# protections.net
KiCad netlist of a schematic drawn in Altium Designer
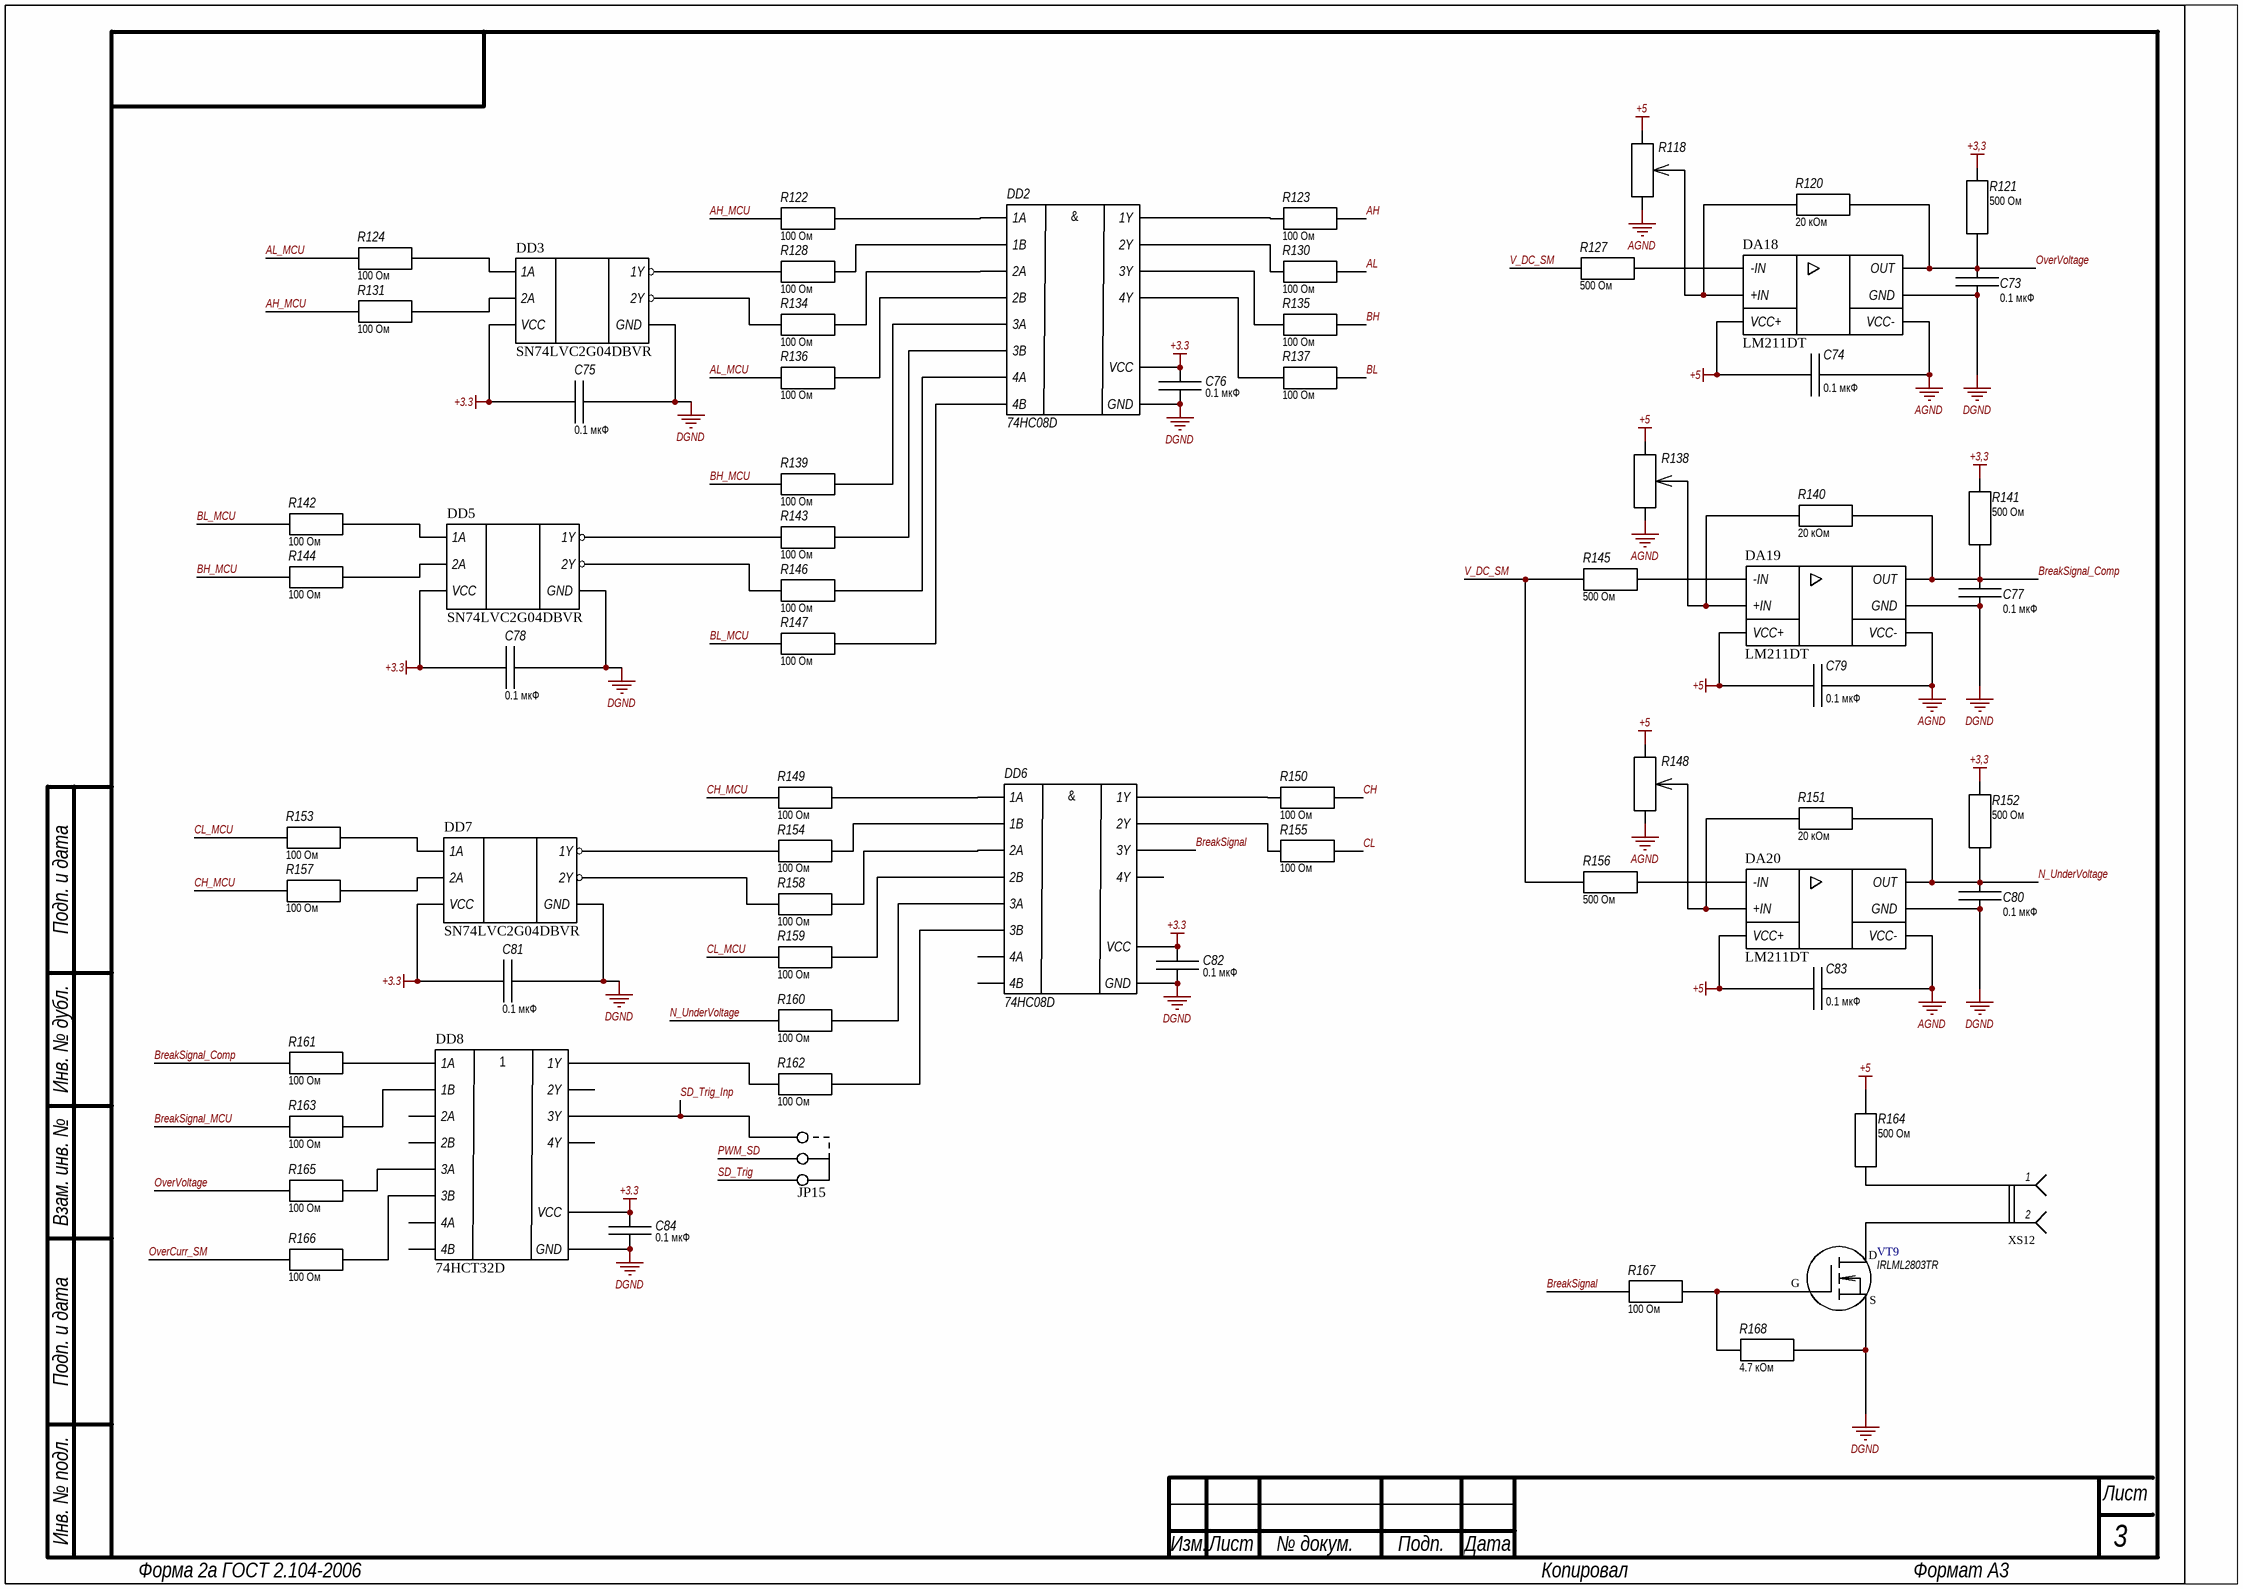
[diagram p0: protections.SchDoc]

(export (version "E")
  (design (tool "Eeschema 10.0.6"))
  (components
    (comp (ref "C73")
      (value "0.1 мкФ")
      (footprint "CC0603")
      (fields (field (name "VOLTAGE") "16В") (field (name "Comment") "Capacitor"))
      (libsource (lib "Main_components") (part "Capacitor"))
    )
    (comp (ref "C74")
      (value "0.1 мкФ")
      (footprint "CC0603")
      (fields (field (name "VOLTAGE") "16В") (field (name "Comment") "Capacitor"))
      (libsource (lib "Main_components") (part "Capacitor"))
    )
    (comp (ref "C75")
      (value "0.1 мкФ")
      (footprint "CC0603")
      (fields (field (name "VOLTAGE") "16В") (field (name "Comment") "Capacitor"))
      (libsource (lib "Main_components") (part "Capacitor"))
    )
    (comp (ref "C76")
      (value "0.1 мкФ")
      (footprint "CC0603")
      (fields (field (name "VOLTAGE") "16В") (field (name "Comment") "Capacitor"))
      (libsource (lib "Main_components") (part "Capacitor"))
    )
    (comp (ref "C77")
      (value "0.1 мкФ")
      (footprint "CC0603")
      (fields (field (name "VOLTAGE") "16В") (field (name "Comment") "Capacitor"))
      (libsource (lib "Main_components") (part "Capacitor"))
    )
    (comp (ref "C78")
      (value "0.1 мкФ")
      (footprint "CC0603")
      (fields (field (name "VOLTAGE") "16В") (field (name "Comment") "Capacitor"))
      (libsource (lib "Main_components") (part "Capacitor"))
    )
    (comp (ref "C79")
      (value "0.1 мкФ")
      (footprint "CC0603")
      (fields (field (name "VOLTAGE") "16В") (field (name "Comment") "Capacitor"))
      (libsource (lib "Main_components") (part "Capacitor"))
    )
    (comp (ref "C80")
      (value "0.1 мкФ")
      (footprint "CC0603")
      (fields (field (name "VOLTAGE") "16В") (field (name "Comment") "Capacitor"))
      (libsource (lib "Main_components") (part "Capacitor"))
    )
    (comp (ref "C81")
      (value "0.1 мкФ")
      (footprint "CC0603")
      (fields (field (name "VOLTAGE") "16В") (field (name "Comment") "Capacitor"))
      (libsource (lib "Main_components") (part "Capacitor"))
    )
    (comp (ref "C82")
      (value "0.1 мкФ")
      (footprint "CC0603")
      (fields (field (name "VOLTAGE") "16В") (field (name "Comment") "Capacitor"))
      (libsource (lib "Main_components") (part "Capacitor"))
    )
    (comp (ref "C83")
      (value "0.1 мкФ")
      (footprint "CC0603")
      (fields (field (name "VOLTAGE") "16В") (field (name "Comment") "Capacitor"))
      (libsource (lib "Main_components") (part "Capacitor"))
    )
    (comp (ref "C84")
      (value "0.1 мкФ")
      (footprint "CC0603")
      (fields (field (name "VOLTAGE") "16В") (field (name "Comment") "Capacitor"))
      (libsource (lib "Main_components") (part "Capacitor"))
    )
    (comp (ref "DA18")
      (value "LM211DT")
      (footprint "SO8")
      (description "Компаратор")
      (libsource (lib "Microcircuits") (part "LM211DT"))
    )
    (comp (ref "DA19")
      (value "LM211DT")
      (footprint "SO8")
      (description "Компаратор")
      (libsource (lib "Microcircuits") (part "LM211DT"))
    )
    (comp (ref "DA20")
      (value "LM211DT")
      (footprint "SO8")
      (description "Компаратор")
      (libsource (lib "Microcircuits") (part "LM211DT"))
    )
    (comp (ref "DD2")
      (value "74HC08D")
      (footprint "SO14")
      (description "Логическая ИС, логическая функция 2И [SO-14]")
      (libsource (lib "Microcircuits") (part "74HC08D"))
    )
    (comp (ref "DD3")
      (value "SN74LVC2G04DBVR")
      (footprint "SOT-23-6")
      (description "Двойной инвертер [SOT-23-6]")
      (libsource (lib "Microcircuits") (part "SN74LVC2G04DBVR"))
    )
    (comp (ref "DD5")
      (value "SN74LVC2G04DBVR")
      (footprint "SOT-23-6")
      (description "Двойной инвертер [SOT-23-6]")
      (libsource (lib "Microcircuits") (part "SN74LVC2G04DBVR"))
    )
    (comp (ref "DD6")
      (value "74HC08D")
      (footprint "SO14")
      (description "Логическая ИС, логическая функция 2И [SO-14]")
      (libsource (lib "Microcircuits") (part "74HC08D"))
    )
    (comp (ref "DD7")
      (value "SN74LVC2G04DBVR")
      (footprint "SOT-23-6")
      (description "Двойной инвертер [SOT-23-6]")
      (libsource (lib "Microcircuits") (part "SN74LVC2G04DBVR"))
    )
    (comp (ref "DD8")
      (value "74HCT32D")
      (footprint "SO14")
      (description "Логическая ИС, логическая функция 2ИЛИ [SO-14]")
      (libsource (lib "Microcircuits") (part "74HCT32D"))
    )
    (comp (ref "JP15") (value "Jumper") (footprint "PLS3") (libsource (lib "Connectors") (part "Jumper")))
    (comp (ref "R118") (value "pot") (footprint "3296W") (libsource (lib "Main_components") (part "pot")))
    (comp (ref "R120")
      (value "20 кОм")
      (footprint "RC0805")
      (fields (field (name "POWER") "125 мВт") (field (name "Comment") "Resistor"))
      (libsource (lib "Main_components") (part "Resistor"))
    )
    (comp (ref "R121")
      (value "500 Ом")
      (footprint "RC0805")
      (fields (field (name "POWER") "125 мВт") (field (name "Comment") "Resistor"))
      (libsource (lib "Main_components") (part "Resistor"))
    )
    (comp (ref "R122")
      (value "100 Ом")
      (footprint "RC0603")
      (fields (field (name "POWER") "100 мВт") (field (name "Comment") "Resistor"))
      (libsource (lib "Main_components") (part "Resistor"))
    )
    (comp (ref "R123")
      (value "100 Ом")
      (footprint "RC0603")
      (fields (field (name "POWER") "100 мВт") (field (name "Comment") "Resistor"))
      (libsource (lib "Main_components") (part "Resistor"))
    )
    (comp (ref "R124")
      (value "100 Ом")
      (footprint "RC0603")
      (fields (field (name "POWER") "100 мВт") (field (name "Comment") "Resistor"))
      (libsource (lib "Main_components") (part "Resistor"))
    )
    (comp (ref "R127")
      (value "500 Ом")
      (footprint "RC0805")
      (fields (field (name "POWER") "125 мВт") (field (name "Comment") "Resistor"))
      (libsource (lib "Main_components") (part "Resistor"))
    )
    (comp (ref "R128")
      (value "100 Ом")
      (footprint "RC0603")
      (fields (field (name "POWER") "100 мВт") (field (name "Comment") "Resistor"))
      (libsource (lib "Main_components") (part "Resistor"))
    )
    (comp (ref "R130")
      (value "100 Ом")
      (footprint "RC0603")
      (fields (field (name "POWER") "100 мВт") (field (name "Comment") "Resistor"))
      (libsource (lib "Main_components") (part "Resistor"))
    )
    (comp (ref "R131")
      (value "100 Ом")
      (footprint "RC0603")
      (fields (field (name "POWER") "100 мВт") (field (name "Comment") "Resistor"))
      (libsource (lib "Main_components") (part "Resistor"))
    )
    (comp (ref "R134")
      (value "100 Ом")
      (footprint "RC0603")
      (fields (field (name "POWER") "100 мВт") (field (name "Comment") "Resistor"))
      (libsource (lib "Main_components") (part "Resistor"))
    )
    (comp (ref "R135")
      (value "100 Ом")
      (footprint "RC0603")
      (fields (field (name "POWER") "100 мВт") (field (name "Comment") "Resistor"))
      (libsource (lib "Main_components") (part "Resistor"))
    )
    (comp (ref "R136")
      (value "100 Ом")
      (footprint "RC0603")
      (fields (field (name "POWER") "100 мВт") (field (name "Comment") "Resistor"))
      (libsource (lib "Main_components") (part "Resistor"))
    )
    (comp (ref "R137")
      (value "100 Ом")
      (footprint "RC0603")
      (fields (field (name "POWER") "100 мВт") (field (name "Comment") "Resistor"))
      (libsource (lib "Main_components") (part "Resistor"))
    )
    (comp (ref "R138") (value "pot") (footprint "3296W") (libsource (lib "Main_components") (part "pot")))
    (comp (ref "R139")
      (value "100 Ом")
      (footprint "RC0603")
      (fields (field (name "POWER") "100 мВт") (field (name "Comment") "Resistor"))
      (libsource (lib "Main_components") (part "Resistor"))
    )
    (comp (ref "R140")
      (value "20 кОм")
      (footprint "RC0805")
      (fields (field (name "POWER") "125 мВт") (field (name "Comment") "Resistor"))
      (libsource (lib "Main_components") (part "Resistor"))
    )
    (comp (ref "R141")
      (value "500 Ом")
      (footprint "RC0805")
      (fields (field (name "POWER") "125 мВт") (field (name "Comment") "Resistor"))
      (libsource (lib "Main_components") (part "Resistor"))
    )
    (comp (ref "R142")
      (value "100 Ом")
      (footprint "RC0603")
      (fields (field (name "POWER") "100 мВт") (field (name "Comment") "Resistor"))
      (libsource (lib "Main_components") (part "Resistor"))
    )
    (comp (ref "R143")
      (value "100 Ом")
      (footprint "RC0603")
      (fields (field (name "POWER") "100 мВт") (field (name "Comment") "Resistor"))
      (libsource (lib "Main_components") (part "Resistor"))
    )
    (comp (ref "R144")
      (value "100 Ом")
      (footprint "RC0603")
      (fields (field (name "POWER") "100 мВт") (field (name "Comment") "Resistor"))
      (libsource (lib "Main_components") (part "Resistor"))
    )
    (comp (ref "R145")
      (value "500 Ом")
      (footprint "RC0805")
      (fields (field (name "POWER") "125 мВт") (field (name "Comment") "Resistor"))
      (libsource (lib "Main_components") (part "Resistor"))
    )
    (comp (ref "R146")
      (value "100 Ом")
      (footprint "RC0603")
      (fields (field (name "POWER") "100 мВт") (field (name "Comment") "Resistor"))
      (libsource (lib "Main_components") (part "Resistor"))
    )
    (comp (ref "R147")
      (value "100 Ом")
      (footprint "RC0603")
      (fields (field (name "POWER") "100 мВт") (field (name "Comment") "Resistor"))
      (libsource (lib "Main_components") (part "Resistor"))
    )
    (comp (ref "R148") (value "pot") (footprint "3296W") (libsource (lib "Main_components") (part "pot")))
    (comp (ref "R149")
      (value "100 Ом")
      (footprint "RC0603")
      (fields (field (name "POWER") "100 мВт") (field (name "Comment") "Resistor"))
      (libsource (lib "Main_components") (part "Resistor"))
    )
    (comp (ref "R150")
      (value "100 Ом")
      (footprint "RC0603")
      (fields (field (name "POWER") "100 мВт") (field (name "Comment") "Resistor"))
      (libsource (lib "Main_components") (part "Resistor"))
    )
    (comp (ref "R151")
      (value "20 кОм")
      (footprint "RC0805")
      (fields (field (name "POWER") "125 мВт") (field (name "Comment") "Resistor"))
      (libsource (lib "Main_components") (part "Resistor"))
    )
    (comp (ref "R152")
      (value "500 Ом")
      (footprint "RC0805")
      (fields (field (name "POWER") "125 мВт") (field (name "Comment") "Resistor"))
      (libsource (lib "Main_components") (part "Resistor"))
    )
    (comp (ref "R153")
      (value "100 Ом")
      (footprint "RC0603")
      (fields (field (name "POWER") "100 мВт") (field (name "Comment") "Resistor"))
      (libsource (lib "Main_components") (part "Resistor"))
    )
    (comp (ref "R154")
      (value "100 Ом")
      (footprint "RC0603")
      (fields (field (name "POWER") "100 мВт") (field (name "Comment") "Resistor"))
      (libsource (lib "Main_components") (part "Resistor"))
    )
    (comp (ref "R155")
      (value "100 Ом")
      (footprint "RC0603")
      (fields (field (name "POWER") "100 мВт") (field (name "Comment") "Resistor"))
      (libsource (lib "Main_components") (part "Resistor"))
    )
    (comp (ref "R156")
      (value "500 Ом")
      (footprint "RC0805")
      (fields (field (name "POWER") "125 мВт") (field (name "Comment") "Resistor"))
      (libsource (lib "Main_components") (part "Resistor"))
    )
    (comp (ref "R157")
      (value "100 Ом")
      (footprint "RC0603")
      (fields (field (name "POWER") "100 мВт") (field (name "Comment") "Resistor"))
      (libsource (lib "Main_components") (part "Resistor"))
    )
    (comp (ref "R158")
      (value "100 Ом")
      (footprint "RC0603")
      (fields (field (name "POWER") "100 мВт") (field (name "Comment") "Resistor"))
      (libsource (lib "Main_components") (part "Resistor"))
    )
    (comp (ref "R159")
      (value "100 Ом")
      (footprint "RC0603")
      (fields (field (name "POWER") "100 мВт") (field (name "Comment") "Resistor"))
      (libsource (lib "Main_components") (part "Resistor"))
    )
    (comp (ref "R160")
      (value "100 Ом")
      (footprint "RC0603")
      (fields (field (name "POWER") "100 мВт") (field (name "Comment") "Resistor"))
      (libsource (lib "Main_components") (part "Resistor"))
    )
    (comp (ref "R161")
      (value "100 Ом")
      (footprint "RC0603")
      (fields (field (name "POWER") "100 мВт") (field (name "Comment") "Resistor"))
      (libsource (lib "Main_components") (part "Resistor"))
    )
    (comp (ref "R162")
      (value "100 Ом")
      (footprint "RC0603")
      (fields (field (name "POWER") "100 мВт") (field (name "Comment") "Resistor"))
      (libsource (lib "Main_components") (part "Resistor"))
    )
    (comp (ref "R163")
      (value "100 Ом")
      (footprint "RC0603")
      (fields (field (name "POWER") "100 мВт") (field (name "Comment") "Resistor"))
      (libsource (lib "Main_components") (part "Resistor"))
    )
    (comp (ref "R164")
      (value "500 Ом")
      (footprint "RC1206")
      (fields (field (name "POWER") "250 мВт") (field (name "Comment") "Resistor"))
      (libsource (lib "Main_components") (part "Resistor"))
    )
    (comp (ref "R165")
      (value "100 Ом")
      (footprint "RC0603")
      (fields (field (name "POWER") "100 мВт") (field (name "Comment") "Resistor"))
      (libsource (lib "Main_components") (part "Resistor"))
    )
    (comp (ref "R166")
      (value "100 Ом")
      (footprint "RC0603")
      (fields (field (name "POWER") "100 мВт") (field (name "Comment") "Resistor"))
      (libsource (lib "Main_components") (part "Resistor"))
    )
    (comp (ref "R167")
      (value "100 Ом")
      (footprint "RC0603")
      (fields (field (name "POWER") "100 мВт") (field (name "Comment") "Resistor"))
      (libsource (lib "Main_components") (part "Resistor"))
    )
    (comp (ref "R168")
      (value "4.7 кОм")
      (footprint "RC0603")
      (fields (field (name "POWER") "100 мВт") (field (name "Comment") "Resistor"))
      (libsource (lib "Main_components") (part "Resistor"))
    )
    (comp (ref "VT9")
      (value "IRLML2803TR")
      (footprint "SOT-23-3")
      (libsource (lib "Main_components") (part "N-MOSFET"))
    )
    (comp (ref "XS12")
      (value "JST-Male-2")
      (footprint "JST-2")
      (libsource (lib "Connectors") (part "JST-Male-2"))
    )
  )
  (nets
    (net (code "1") (name "+3,3") (class "Default")
      (node (ref "R121") (pin "2") (pinfunction "2_2") (pintype "passive"))
      (node (ref "R141") (pin "2") (pinfunction "2_2") (pintype "passive"))
      (node (ref "R152") (pin "2") (pinfunction "2_2") (pintype "passive"))
    )
    (net (code "2") (name "+3.3") (class "Default")
      (node (ref "C75") (pin "2") (pinfunction "2_2") (pintype "passive"))
      (node (ref "C76") (pin "2") (pinfunction "2_2") (pintype "passive"))
      (node (ref "C78") (pin "2") (pinfunction "2_2") (pintype "passive"))
      (node (ref "C81") (pin "2") (pinfunction "2_2") (pintype "passive"))
      (node (ref "C82") (pin "2") (pinfunction "2_2") (pintype "passive"))
      (node (ref "C84") (pin "2") (pinfunction "2_2") (pintype "passive"))
      (node (ref "DD2") (pin "14") (pinfunction "VCC_14") (pintype "passive"))
      (node (ref "DD3") (pin "5") (pinfunction "VCC_5") (pintype "passive"))
      (node (ref "DD5") (pin "5") (pinfunction "VCC_5") (pintype "passive"))
      (node (ref "DD6") (pin "14") (pinfunction "VCC_14") (pintype "passive"))
      (node (ref "DD7") (pin "5") (pinfunction "VCC_5") (pintype "passive"))
      (node (ref "DD8") (pin "14") (pinfunction "VCC_14") (pintype "passive"))
    )
    (net (code "3") (name "+5") (class "Default")
      (node (ref "C74") (pin "1") (pinfunction "1_1") (pintype "passive"))
      (node (ref "C79") (pin "1") (pinfunction "1_1") (pintype "passive"))
      (node (ref "C83") (pin "1") (pinfunction "1_1") (pintype "passive"))
      (node (ref "DA18") (pin "8") (pinfunction "VCC+_8") (pintype "passive"))
      (node (ref "DA19") (pin "8") (pinfunction "VCC+_8") (pintype "passive"))
      (node (ref "DA20") (pin "8") (pinfunction "VCC+_8") (pintype "passive"))
      (node (ref "R118") (pin "1") (pinfunction "1_1") (pintype "passive"))
      (node (ref "R138") (pin "1") (pinfunction "1_1") (pintype "passive"))
      (node (ref "R148") (pin "1") (pinfunction "1_1") (pintype "passive"))
      (node (ref "R164") (pin "1") (pinfunction "1_1") (pintype "passive"))
    )
    (net (code "4") (name "/AH") (class "Default")
      (node (ref "R123") (pin "1") (pinfunction "1_1") (pintype "passive"))
    )
    (net (code "5") (name "/AH_MCU") (class "Default")
      (node (ref "R122") (pin "2") (pinfunction "2_2") (pintype "passive"))
      (node (ref "R131") (pin "2") (pinfunction "2_2") (pintype "passive"))
    )
    (net (code "6") (name "/AL") (class "Default")
      (node (ref "R130") (pin "1") (pinfunction "1_1") (pintype "passive"))
    )
    (net (code "7") (name "/AL_MCU") (class "Default")
      (node (ref "R124") (pin "2") (pinfunction "2_2") (pintype "passive"))
      (node (ref "R136") (pin "2") (pinfunction "2_2") (pintype "passive"))
    )
    (net (code "8") (name "/BH") (class "Default")
      (node (ref "R135") (pin "1") (pinfunction "1_1") (pintype "passive"))
    )
    (net (code "9") (name "/BH_MCU") (class "Default")
      (node (ref "R139") (pin "2") (pinfunction "2_2") (pintype "passive"))
      (node (ref "R144") (pin "2") (pinfunction "2_2") (pintype "passive"))
    )
    (net (code "10") (name "/BL") (class "Default")
      (node (ref "R137") (pin "1") (pinfunction "1_1") (pintype "passive"))
    )
    (net (code "11") (name "/BL_MCU") (class "Default")
      (node (ref "R142") (pin "2") (pinfunction "2_2") (pintype "passive"))
      (node (ref "R147") (pin "2") (pinfunction "2_2") (pintype "passive"))
    )
    (net (code "12") (name "/BreakSignal") (class "Default")
      (node (ref "DD6") (pin "8") (pinfunction "3Y_8") (pintype "passive"))
      (node (ref "R167") (pin "2") (pinfunction "2_2") (pintype "passive"))
    )
    (net (code "13") (name "/BreakSignal_Comp") (class "Default")
      (node (ref "C77") (pin "2") (pinfunction "2_2") (pintype "passive"))
      (node (ref "DA19") (pin "7") (pinfunction "OUT_7") (pintype "passive"))
      (node (ref "R140") (pin "2") (pinfunction "2_2") (pintype "passive"))
      (node (ref "R141") (pin "1") (pinfunction "1_1") (pintype "passive"))
      (node (ref "R161") (pin "2") (pinfunction "2_2") (pintype "passive"))
    )
    (net (code "14") (name "/BreakSignal_MCU") (class "Default")
      (node (ref "R163") (pin "2") (pinfunction "2_2") (pintype "passive"))
    )
    (net (code "15") (name "/CH") (class "Default")
      (node (ref "R150") (pin "1") (pinfunction "1_1") (pintype "passive"))
    )
    (net (code "16") (name "/CH_MCU") (class "Default")
      (node (ref "R149") (pin "2") (pinfunction "2_2") (pintype "passive"))
      (node (ref "R157") (pin "2") (pinfunction "2_2") (pintype "passive"))
    )
    (net (code "17") (name "/CL") (class "Default")
      (node (ref "R155") (pin "1") (pinfunction "1_1") (pintype "passive"))
    )
    (net (code "18") (name "/CL_MCU") (class "Default")
      (node (ref "R153") (pin "2") (pinfunction "2_2") (pintype "passive"))
      (node (ref "R159") (pin "2") (pinfunction "2_2") (pintype "passive"))
    )
    (net (code "19") (name "/N_UnderVoltage") (class "Default")
      (node (ref "C80") (pin "2") (pinfunction "2_2") (pintype "passive"))
      (node (ref "DA20") (pin "7") (pinfunction "OUT_7") (pintype "passive"))
      (node (ref "R151") (pin "2") (pinfunction "2_2") (pintype "passive"))
      (node (ref "R152") (pin "1") (pinfunction "1_1") (pintype "passive"))
      (node (ref "R160") (pin "2") (pinfunction "2_2") (pintype "passive"))
    )
    (net (code "20") (name "/OverCurr_SM") (class "Default")
      (node (ref "R166") (pin "2") (pinfunction "2_2") (pintype "passive"))
    )
    (net (code "21") (name "/OverVoltage") (class "Default")
      (node (ref "C73") (pin "2") (pinfunction "2_2") (pintype "passive"))
      (node (ref "DA18") (pin "7") (pinfunction "OUT_7") (pintype "passive"))
      (node (ref "R120") (pin "2") (pinfunction "2_2") (pintype "passive"))
      (node (ref "R121") (pin "1") (pinfunction "1_1") (pintype "passive"))
      (node (ref "R165") (pin "2") (pinfunction "2_2") (pintype "passive"))
    )
    (net (code "22") (name "/PWM_SD") (class "Default")
      (node (ref "JP15") (pin "2") (pinfunction "5_2") (pintype "passive"))
    )
    (net (code "23") (name "/SD_Trig") (class "Default")
      (node (ref "JP15") (pin "3") (pinfunction "6_3") (pintype "passive"))
    )
    (net (code "24") (name "/SD_Trig_Inp") (class "Default")
      (node (ref "DD8") (pin "8") (pinfunction "3Y_8") (pintype "passive"))
      (node (ref "JP15") (pin "1") (pinfunction "4_1") (pintype "passive"))
    )
    (net (code "25") (name "/V_DC_SM") (class "Default")
      (node (ref "R127") (pin "1") (pinfunction "1_1") (pintype "passive"))
      (node (ref "R145") (pin "1") (pinfunction "1_1") (pintype "passive"))
      (node (ref "R156") (pin "1") (pinfunction "1_1") (pintype "passive"))
    )
    (net (code "26") (name "AGND") (class "Default")
      (node (ref "C74") (pin "2") (pinfunction "2_2") (pintype "passive"))
      (node (ref "C79") (pin "2") (pinfunction "2_2") (pintype "passive"))
      (node (ref "C83") (pin "2") (pinfunction "2_2") (pintype "passive"))
      (node (ref "DA18") (pin "4") (pinfunction "VCC-_4") (pintype "passive"))
      (node (ref "DA19") (pin "4") (pinfunction "VCC-_4") (pintype "passive"))
      (node (ref "DA20") (pin "4") (pinfunction "VCC-_4") (pintype "passive"))
      (node (ref "R118") (pin "3") (pinfunction "3_3") (pintype "passive"))
      (node (ref "R138") (pin "3") (pinfunction "3_3") (pintype "passive"))
      (node (ref "R148") (pin "3") (pinfunction "3_3") (pintype "passive"))
    )
    (net (code "27") (name "DGND") (class "Default")
      (node (ref "C73") (pin "1") (pinfunction "1_1") (pintype "passive"))
      (node (ref "C75") (pin "1") (pinfunction "1_1") (pintype "passive"))
      (node (ref "C76") (pin "1") (pinfunction "1_1") (pintype "passive"))
      (node (ref "C77") (pin "1") (pinfunction "1_1") (pintype "passive"))
      (node (ref "C78") (pin "1") (pinfunction "1_1") (pintype "passive"))
      (node (ref "C80") (pin "1") (pinfunction "1_1") (pintype "passive"))
      (node (ref "C81") (pin "1") (pinfunction "1_1") (pintype "passive"))
      (node (ref "C82") (pin "1") (pinfunction "1_1") (pintype "passive"))
      (node (ref "C84") (pin "1") (pinfunction "1_1") (pintype "passive"))
      (node (ref "DA18") (pin "1") (pinfunction "GND_1") (pintype "passive"))
      (node (ref "DA19") (pin "1") (pinfunction "GND_1") (pintype "passive"))
      (node (ref "DA20") (pin "1") (pinfunction "GND_1") (pintype "passive"))
      (node (ref "DD2") (pin "7") (pinfunction "GND_7") (pintype "passive"))
      (node (ref "DD3") (pin "2") (pinfunction "GND_2") (pintype "passive"))
      (node (ref "DD5") (pin "2") (pinfunction "GND_2") (pintype "passive"))
      (node (ref "DD6") (pin "7") (pinfunction "GND_7") (pintype "passive"))
      (node (ref "DD7") (pin "2") (pinfunction "GND_2") (pintype "passive"))
      (node (ref "DD8") (pin "7") (pinfunction "GND_7") (pintype "passive"))
      (node (ref "R168") (pin "1") (pinfunction "1_1") (pintype "passive"))
      (node (ref "VT9") (pin "S") (pinfunction "S_S") (pintype "passive"))
    )
    (net (code "28") (name "Net-(DA18-+IN)") (class "Default")
      (node (ref "DA18") (pin "2") (pinfunction "+IN_2") (pintype "passive"))
      (node (ref "R118") (pin "2") (pinfunction "2_2") (pintype "passive"))
      (node (ref "R120") (pin "1") (pinfunction "1_1") (pintype "passive"))
    )
    (net (code "29") (name "Net-(DA18--IN)") (class "Default")
      (node (ref "DA18") (pin "3") (pinfunction "-IN_3") (pintype "passive"))
      (node (ref "R127") (pin "2") (pinfunction "2_2") (pintype "passive"))
    )
    (net (code "30") (name "Net-(DA19-+IN)") (class "Default")
      (node (ref "DA19") (pin "2") (pinfunction "+IN_2") (pintype "passive"))
      (node (ref "R138") (pin "2") (pinfunction "2_2") (pintype "passive"))
      (node (ref "R140") (pin "1") (pinfunction "1_1") (pintype "passive"))
    )
    (net (code "31") (name "Net-(DA19--IN)") (class "Default")
      (node (ref "DA19") (pin "3") (pinfunction "-IN_3") (pintype "passive"))
      (node (ref "R145") (pin "2") (pinfunction "2_2") (pintype "passive"))
    )
    (net (code "32") (name "Net-(DA20-+IN)") (class "Default")
      (node (ref "DA20") (pin "2") (pinfunction "+IN_2") (pintype "passive"))
      (node (ref "R148") (pin "2") (pinfunction "2_2") (pintype "passive"))
      (node (ref "R151") (pin "1") (pinfunction "1_1") (pintype "passive"))
    )
    (net (code "33") (name "Net-(DA20--IN)") (class "Default")
      (node (ref "DA20") (pin "3") (pinfunction "-IN_3") (pintype "passive"))
      (node (ref "R156") (pin "2") (pinfunction "2_2") (pintype "passive"))
    )
    (net (code "34") (name "Net-(DD2-1A)") (class "Default")
      (node (ref "DD2") (pin "1") (pinfunction "1A_1") (pintype "passive"))
      (node (ref "R122") (pin "1") (pinfunction "1_1") (pintype "passive"))
    )
    (net (code "35") (name "Net-(DD2-1B)") (class "Default")
      (node (ref "DD2") (pin "2") (pinfunction "1B_2") (pintype "passive"))
      (node (ref "R128") (pin "1") (pinfunction "1_1") (pintype "passive"))
    )
    (net (code "36") (name "Net-(DD2-1Y)") (class "Default")
      (node (ref "DD2") (pin "3") (pinfunction "1Y_3") (pintype "passive"))
      (node (ref "R123") (pin "2") (pinfunction "2_2") (pintype "passive"))
    )
    (net (code "37") (name "Net-(DD2-2A)") (class "Default")
      (node (ref "DD2") (pin "4") (pinfunction "2A_4") (pintype "passive"))
      (node (ref "R134") (pin "1") (pinfunction "1_1") (pintype "passive"))
    )
    (net (code "38") (name "Net-(DD2-2B)") (class "Default")
      (node (ref "DD2") (pin "5") (pinfunction "2B_5") (pintype "passive"))
      (node (ref "R136") (pin "1") (pinfunction "1_1") (pintype "passive"))
    )
    (net (code "39") (name "Net-(DD2-2Y)") (class "Default")
      (node (ref "DD2") (pin "6") (pinfunction "2Y_6") (pintype "passive"))
      (node (ref "R130") (pin "2") (pinfunction "2_2") (pintype "passive"))
    )
    (net (code "40") (name "Net-(DD2-3A)") (class "Default")
      (node (ref "DD2") (pin "9") (pinfunction "3A_9") (pintype "passive"))
      (node (ref "R139") (pin "1") (pinfunction "1_1") (pintype "passive"))
    )
    (net (code "41") (name "Net-(DD2-3B)") (class "Default")
      (node (ref "DD2") (pin "10") (pinfunction "3B_10") (pintype "passive"))
      (node (ref "R143") (pin "1") (pinfunction "1_1") (pintype "passive"))
    )
    (net (code "42") (name "Net-(DD2-3Y)") (class "Default")
      (node (ref "DD2") (pin "8") (pinfunction "3Y_8") (pintype "passive"))
      (node (ref "R135") (pin "2") (pinfunction "2_2") (pintype "passive"))
    )
    (net (code "43") (name "Net-(DD2-4A)") (class "Default")
      (node (ref "DD2") (pin "12") (pinfunction "4A_12") (pintype "passive"))
      (node (ref "R146") (pin "1") (pinfunction "1_1") (pintype "passive"))
    )
    (net (code "44") (name "Net-(DD2-4B)") (class "Default")
      (node (ref "DD2") (pin "13") (pinfunction "4B_13") (pintype "passive"))
      (node (ref "R147") (pin "1") (pinfunction "1_1") (pintype "passive"))
    )
    (net (code "45") (name "Net-(DD2-4Y)") (class "Default")
      (node (ref "DD2") (pin "11") (pinfunction "4Y_11") (pintype "passive"))
      (node (ref "R137") (pin "2") (pinfunction "2_2") (pintype "passive"))
    )
    (net (code "46") (name "Net-(DD3-1A)") (class "Default")
      (node (ref "DD3") (pin "1") (pinfunction "1A_1") (pintype "passive"))
      (node (ref "R124") (pin "1") (pinfunction "1_1") (pintype "passive"))
    )
    (net (code "47") (name "Net-(DD3-1Y)") (class "Default")
      (node (ref "DD3") (pin "6") (pinfunction "1Y_6") (pintype "passive"))
      (node (ref "R128") (pin "2") (pinfunction "2_2") (pintype "passive"))
    )
    (net (code "48") (name "Net-(DD3-2A)") (class "Default")
      (node (ref "DD3") (pin "3") (pinfunction "2A_3") (pintype "passive"))
      (node (ref "R131") (pin "1") (pinfunction "1_1") (pintype "passive"))
    )
    (net (code "49") (name "Net-(DD3-2Y)") (class "Default")
      (node (ref "DD3") (pin "4") (pinfunction "2Y_4") (pintype "passive"))
      (node (ref "R134") (pin "2") (pinfunction "2_2") (pintype "passive"))
    )
    (net (code "50") (name "Net-(DD5-1A)") (class "Default")
      (node (ref "DD5") (pin "1") (pinfunction "1A_1") (pintype "passive"))
      (node (ref "R142") (pin "1") (pinfunction "1_1") (pintype "passive"))
    )
    (net (code "51") (name "Net-(DD5-1Y)") (class "Default")
      (node (ref "DD5") (pin "6") (pinfunction "1Y_6") (pintype "passive"))
      (node (ref "R143") (pin "2") (pinfunction "2_2") (pintype "passive"))
    )
    (net (code "52") (name "Net-(DD5-2A)") (class "Default")
      (node (ref "DD5") (pin "3") (pinfunction "2A_3") (pintype "passive"))
      (node (ref "R144") (pin "1") (pinfunction "1_1") (pintype "passive"))
    )
    (net (code "53") (name "Net-(DD5-2Y)") (class "Default")
      (node (ref "DD5") (pin "4") (pinfunction "2Y_4") (pintype "passive"))
      (node (ref "R146") (pin "2") (pinfunction "2_2") (pintype "passive"))
    )
    (net (code "54") (name "Net-(DD6-1A)") (class "Default")
      (node (ref "DD6") (pin "1") (pinfunction "1A_1") (pintype "passive"))
      (node (ref "R149") (pin "1") (pinfunction "1_1") (pintype "passive"))
    )
    (net (code "55") (name "Net-(DD6-1B)") (class "Default")
      (node (ref "DD6") (pin "2") (pinfunction "1B_2") (pintype "passive"))
      (node (ref "R154") (pin "1") (pinfunction "1_1") (pintype "passive"))
    )
    (net (code "56") (name "Net-(DD6-1Y)") (class "Default")
      (node (ref "DD6") (pin "3") (pinfunction "1Y_3") (pintype "passive"))
      (node (ref "R150") (pin "2") (pinfunction "2_2") (pintype "passive"))
    )
    (net (code "57") (name "Net-(DD6-2A)") (class "Default")
      (node (ref "DD6") (pin "4") (pinfunction "2A_4") (pintype "passive"))
      (node (ref "R158") (pin "1") (pinfunction "1_1") (pintype "passive"))
    )
    (net (code "58") (name "Net-(DD6-2B)") (class "Default")
      (node (ref "DD6") (pin "5") (pinfunction "2B_5") (pintype "passive"))
      (node (ref "R159") (pin "1") (pinfunction "1_1") (pintype "passive"))
    )
    (net (code "59") (name "Net-(DD6-2Y)") (class "Default")
      (node (ref "DD6") (pin "6") (pinfunction "2Y_6") (pintype "passive"))
      (node (ref "R155") (pin "2") (pinfunction "2_2") (pintype "passive"))
    )
    (net (code "60") (name "Net-(DD6-3A)") (class "Default")
      (node (ref "DD6") (pin "9") (pinfunction "3A_9") (pintype "passive"))
      (node (ref "R160") (pin "1") (pinfunction "1_1") (pintype "passive"))
    )
    (net (code "61") (name "Net-(DD6-3B)") (class "Default")
      (node (ref "DD6") (pin "10") (pinfunction "3B_10") (pintype "passive"))
      (node (ref "R162") (pin "1") (pinfunction "1_1") (pintype "passive"))
    )
    (net (code "62") (name "Net-(DD7-1A)") (class "Default")
      (node (ref "DD7") (pin "1") (pinfunction "1A_1") (pintype "passive"))
      (node (ref "R153") (pin "1") (pinfunction "1_1") (pintype "passive"))
    )
    (net (code "63") (name "Net-(DD7-1Y)") (class "Default")
      (node (ref "DD7") (pin "6") (pinfunction "1Y_6") (pintype "passive"))
      (node (ref "R154") (pin "2") (pinfunction "2_2") (pintype "passive"))
    )
    (net (code "64") (name "Net-(DD7-2A)") (class "Default")
      (node (ref "DD7") (pin "3") (pinfunction "2A_3") (pintype "passive"))
      (node (ref "R157") (pin "1") (pinfunction "1_1") (pintype "passive"))
    )
    (net (code "65") (name "Net-(DD7-2Y)") (class "Default")
      (node (ref "DD7") (pin "4") (pinfunction "2Y_4") (pintype "passive"))
      (node (ref "R158") (pin "2") (pinfunction "2_2") (pintype "passive"))
    )
    (net (code "66") (name "Net-(DD8-1A)") (class "Default")
      (node (ref "DD8") (pin "1") (pinfunction "1A_1") (pintype "passive"))
      (node (ref "R161") (pin "1") (pinfunction "1_1") (pintype "passive"))
    )
    (net (code "67") (name "Net-(DD8-1B)") (class "Default")
      (node (ref "DD8") (pin "2") (pinfunction "1B_2") (pintype "passive"))
      (node (ref "R163") (pin "1") (pinfunction "1_1") (pintype "passive"))
    )
    (net (code "68") (name "Net-(DD8-1Y)") (class "Default")
      (node (ref "DD8") (pin "3") (pinfunction "1Y_3") (pintype "passive"))
      (node (ref "R162") (pin "2") (pinfunction "2_2") (pintype "passive"))
    )
    (net (code "69") (name "Net-(DD8-3A)") (class "Default")
      (node (ref "DD8") (pin "9") (pinfunction "3A_9") (pintype "passive"))
      (node (ref "R165") (pin "1") (pinfunction "1_1") (pintype "passive"))
    )
    (net (code "70") (name "Net-(DD8-3B)") (class "Default")
      (node (ref "DD8") (pin "10") (pinfunction "3B_10") (pintype "passive"))
      (node (ref "R166") (pin "1") (pinfunction "1_1") (pintype "passive"))
    )
    (net (code "71") (name "Net-(R164-Pad2)") (class "Default")
      (node (ref "R164") (pin "2") (pinfunction "2_2") (pintype "passive"))
      (node (ref "XS12") (pin "1") (pinfunction "1_1") (pintype "passive"))
    )
    (net (code "72") (name "Net-(R167-Pad1)") (class "Default")
      (node (ref "R167") (pin "1") (pinfunction "1_1") (pintype "passive"))
      (node (ref "R168") (pin "2") (pinfunction "2_2") (pintype "passive"))
      (node (ref "VT9") (pin "G") (pinfunction "G_G") (pintype "passive"))
    )
    (net (code "73") (name "Net-(VT9-PadD)") (class "Default")
      (node (ref "VT9") (pin "D") (pinfunction "D_D") (pintype "passive"))
      (node (ref "XS12") (pin "2") (pinfunction "2_2") (pintype "passive"))
    )
    (net (code "74") (name "unconnected-(DD6-4A-Pad12)") (class "Default")
      (node (ref "DD6") (pin "12") (pinfunction "4A_12") (pintype "passive"))
    )
    (net (code "75") (name "unconnected-(DD6-4B-Pad13)") (class "Default")
      (node (ref "DD6") (pin "13") (pinfunction "4B_13") (pintype "passive"))
    )
    (net (code "76") (name "unconnected-(DD6-4Y-Pad11)") (class "Default")
      (node (ref "DD6") (pin "11") (pinfunction "4Y_11") (pintype "passive"))
    )
    (net (code "77") (name "unconnected-(DD8-2A-Pad4)") (class "Default")
      (node (ref "DD8") (pin "4") (pinfunction "2A_4") (pintype "passive"))
    )
    (net (code "78") (name "unconnected-(DD8-2B-Pad5)") (class "Default")
      (node (ref "DD8") (pin "5") (pinfunction "2B_5") (pintype "passive"))
    )
    (net (code "79") (name "unconnected-(DD8-2Y-Pad6)") (class "Default")
      (node (ref "DD8") (pin "6") (pinfunction "2Y_6") (pintype "passive"))
    )
    (net (code "80") (name "unconnected-(DD8-4A-Pad12)") (class "Default")
      (node (ref "DD8") (pin "12") (pinfunction "4A_12") (pintype "passive"))
    )
    (net (code "81") (name "unconnected-(DD8-4B-Pad13)") (class "Default")
      (node (ref "DD8") (pin "13") (pinfunction "4B_13") (pintype "passive"))
    )
    (net (code "82") (name "unconnected-(DD8-4Y-Pad11)") (class "Default")
      (node (ref "DD8") (pin "11") (pinfunction "4Y_11") (pintype "passive"))
    )
  )
)
